# UCC27444_GateDrivers.net
KiCad netlist of a schematic drawn in Altium Designer
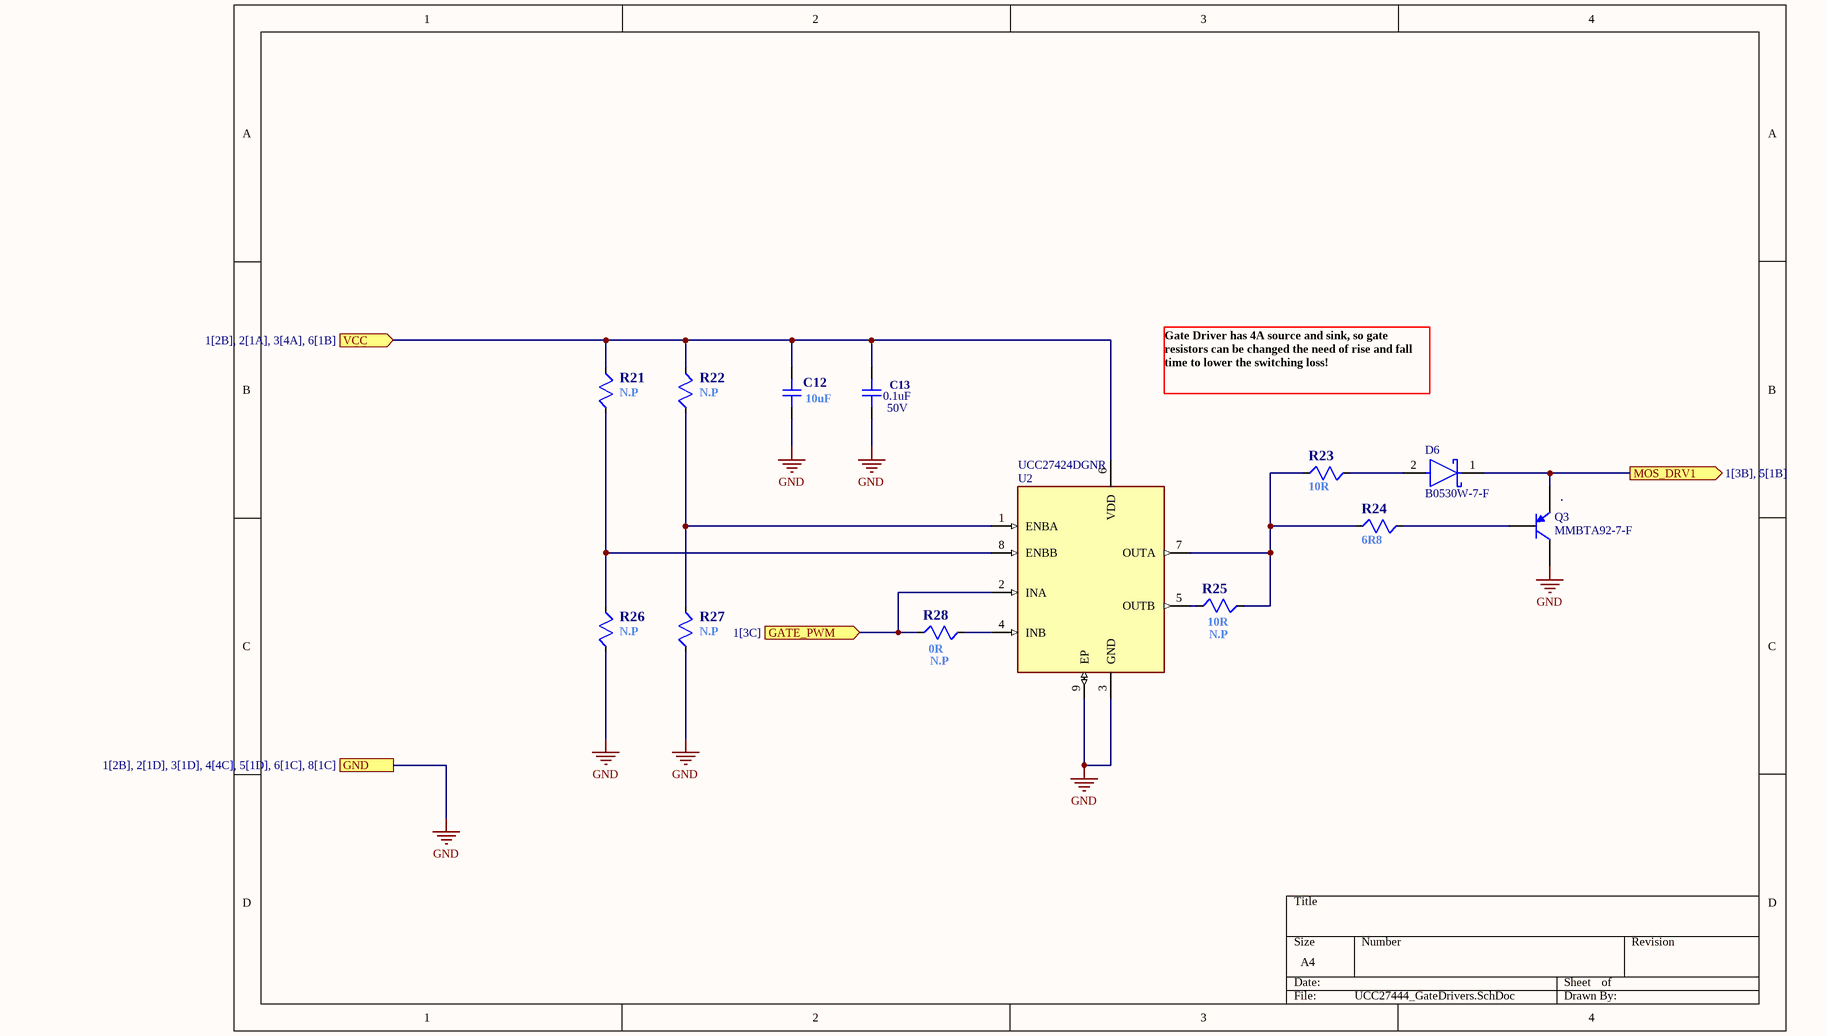
[diagram p0: UCC27444_GateDrivers.SchDoc]

(export (version "E")
  (design (tool "Eeschema 10.0.6"))
  (components
    (comp (ref "C12")
      (value "10uF")
      (footprint "CAP_0805")
      (description "MLCC (2012) 0805 10uF 25VDC ±10% X5R")
      (fields
        (field (name "MANUFACTURER") "YAGEO")
        (field (name "MANUFACTURER PART NUMBER") "CC0805KKX7R9BB105")
      )
      (libsource (lib "Phil-lab") (part "CAP_0805"))
    )
    (comp (ref "C13")
      (value "0.1uF")
      (footprint "CAPC1608N")
      (description "MLCC (1608) 0603 100nF 50VDC ±10% X7R")
      (fields (field (name "RATING") "50V") (field (name "Comment") "CL10B104KB8NNNC"))
      (libsource (lib "WG_MainBoard_NV2") (part "CAP_0805"))
    )
    (comp (ref "D6")
      (value "B0530W-7-F")
      (footprint "FP-SOD123-MFG")
      (description "DIODE SCHOTTKY 30V 500MA SOD123")
      (fields
        (field (name "MANUFACTURER") "Diodes Inc.")
        (field (name "OCTOPART") "https://octopart.com/b0530w-7-f-diodes+inc.-325721")
      )
      (libsource (lib "Altium Content Vault") (part "1d6ec82d83fb6aee721767c19dac4b9"))
    )
    (comp (ref "Q3")
      (value "MMBTA92-7-F")
      (footprint "DIOD-SOT23-3_V")
      (description "PNP Small Signal Transisitor, 500 mA, 300 mW, -55 to 150 degC, 3-Pin SOT23, RoHS, Tape and Reel")
      (fields (field (name "MANUFACTURER") "DiodesIncorporated"))
      (libsource (lib "Altium Content Vault") (part "BJT-PNP-BEC-3"))
    )
    (comp (ref "R21")
      (value "N.P")
      (footprint "RESC1608N")
      (description "0.1W, 1/10W Chip Resistor 0603 (1608 Metric)")
      (libsource (lib "*") (part "RES"))
    )
    (comp (ref "R22")
      (value "N.P")
      (footprint "RESC1608N")
      (description "0.1W, 1/10W Chip Resistor 0603 (1608 Metric)")
      (libsource (lib "*") (part "RES"))
    )
    (comp (ref "R23")
      (value "10R")
      (footprint "PCB_EZ_BuckPowerDriver V3.0:RESC1608N")
      (description "RES.(1608) 0603 10 Ohms 5% 1/10W-S 400PPM")
      (fields (field (name "Comment") "0603SAJ0100T5E"))
      (libsource (lib "WG_MainBoard_NV1") (part "RES"))
    )
    (comp (ref "R24")
      (value "6R8")
      (footprint "PCB_EZ_BuckPowerDriver V2.0:RESC1608N")
      (description "RES.(1608) 0603 6.8 Ohms 5% 1/10W-S 400PPM")
      (fields (field (name "Comment") "0603SAJ068JT5E"))
      (libsource (lib "WG_MainBoard_NV1") (part "RES"))
    )
    (comp (ref "R25")
      (value "N.P")
      (footprint "PCB_EZ_BuckPowerDriver V3.0:RESC1608N")
      (description "RES.(1608) 0603 10 Ohms 5% 1/10W-S 400PPM")
      (fields (field (name "ALTIUM_VALUE") "10R"))
      (libsource (lib "WG_MainBoard_NV1") (part "RES"))
    )
    (comp (ref "R26")
      (value "N.P")
      (footprint "RESC1608N")
      (description "0.1W, 1/10W Chip Resistor 0603 (1608 Metric)")
      (libsource (lib "*") (part "RES"))
    )
    (comp (ref "R27")
      (value "N.P")
      (footprint "RESC1608N")
      (description "0.1W, 1/10W Chip Resistor 0603 (1608 Metric)")
      (libsource (lib "*") (part "RES"))
    )
    (comp (ref "R28")
      (value "N.P")
      (footprint "PCB_EZ_BuckPowerDriver V3.0:RESC1608N")
      (description "RES.(1608) 0603 10 Ohms 5% 1/10W-S 400PPM")
      (fields (field (name "ALTIUM_VALUE") "0R"))
      (libsource (lib "WG_MainBoard_NV1") (part "RES"))
    )
    (comp (ref "U2")
      (value "UCC27424DGNR")
      (footprint "SOP65P490X110-9N")
      (description "Dual Low-Side Gate Driver IC Non-Inverting 8-HVSSOP")
      (fields (field (name "MF") "{'manufacturer': u'Texas Instruments'}"))
      (libsource (lib "Görev Yükü's Libary") (part "UCC27424DGNR"))
    )
  )
  (nets
    (net (code "1") (name "/GATE_PWM") (class "Default")
      (node (ref "R28") (pin "2") (pinfunction "2_2") (pintype "passive"))
      (node (ref "U2") (pin "2") (pinfunction "INA_2") (pintype "input"))
    )
    (net (code "2") (name "/MOS_DRV1") (class "Default")
      (node (ref "D6") (pin "1") (pinfunction "C_1") (pintype "passive"))
      (node (ref "Q3") (pin "2") (pinfunction "E_2") (pintype "passive"))
    )
    (net (code "3") (name "/VCC") (class "Default")
      (node (ref "C12") (pin "2") (pinfunction "2_2") (pintype "passive"))
      (node (ref "C13") (pin "2") (pinfunction "2_2") (pintype "passive"))
      (node (ref "R21") (pin "1") (pinfunction "1_1") (pintype "passive"))
      (node (ref "R22") (pin "1") (pinfunction "1_1") (pintype "passive"))
      (node (ref "U2") (pin "6") (pinfunction "VDD_6") (pintype "power_in"))
    )
    (net (code "4") (name "GND") (class "Default")
      (node (ref "C12") (pin "1") (pinfunction "1_1") (pintype "passive"))
      (node (ref "C13") (pin "1") (pinfunction "1_1") (pintype "passive"))
      (node (ref "Q3") (pin "3") (pinfunction "C_3") (pintype "passive"))
      (node (ref "R26") (pin "2") (pinfunction "2_2") (pintype "passive"))
      (node (ref "R27") (pin "2") (pinfunction "2_2") (pintype "passive"))
      (node (ref "U2") (pin "3") (pinfunction "GND_3") (pintype "power_in"))
      (node (ref "U2") (pin "9") (pinfunction "EP_9") (pintype "bidirectional"))
    )
    (net (code "5") (name "Net-(D6-A)") (class "Default")
      (node (ref "D6") (pin "2") (pinfunction "A_2") (pintype "passive"))
      (node (ref "R23") (pin "1") (pinfunction "1_1") (pintype "passive"))
    )
    (net (code "6") (name "Net-(Q3-B)") (class "Default")
      (node (ref "Q3") (pin "1") (pinfunction "B_1") (pintype "passive"))
      (node (ref "R24") (pin "1") (pinfunction "1_1") (pintype "passive"))
    )
    (net (code "7") (name "Net-(U2-ENBA)") (class "Default")
      (node (ref "R22") (pin "2") (pinfunction "2_2") (pintype "passive"))
      (node (ref "R27") (pin "1") (pinfunction "1_1") (pintype "passive"))
      (node (ref "U2") (pin "1") (pinfunction "ENBA_1") (pintype "input"))
    )
    (net (code "8") (name "Net-(U2-ENBB)") (class "Default")
      (node (ref "R21") (pin "2") (pinfunction "2_2") (pintype "passive"))
      (node (ref "R26") (pin "1") (pinfunction "1_1") (pintype "passive"))
      (node (ref "U2") (pin "8") (pinfunction "ENBB_8") (pintype "input"))
    )
    (net (code "9") (name "Net-(U2-INB)") (class "Default")
      (node (ref "R28") (pin "1") (pinfunction "1_1") (pintype "passive"))
      (node (ref "U2") (pin "4") (pinfunction "INB_4") (pintype "input"))
    )
    (net (code "10") (name "Net-(U2-OUTA)") (class "Default")
      (node (ref "R23") (pin "2") (pinfunction "2_2") (pintype "passive"))
      (node (ref "R24") (pin "2") (pinfunction "2_2") (pintype "passive"))
      (node (ref "R25") (pin "1") (pinfunction "1_1") (pintype "passive"))
      (node (ref "U2") (pin "7") (pinfunction "OUTA_7") (pintype "output"))
    )
    (net (code "11") (name "Net-(U2-OUTB)") (class "Default")
      (node (ref "R25") (pin "2") (pinfunction "2_2") (pintype "passive"))
      (node (ref "U2") (pin "5") (pinfunction "OUTB_5") (pintype "output"))
    )
  )
)
